# cryobondr-qbit2.net
KiCad netlist of a schematic drawn in EAGLE
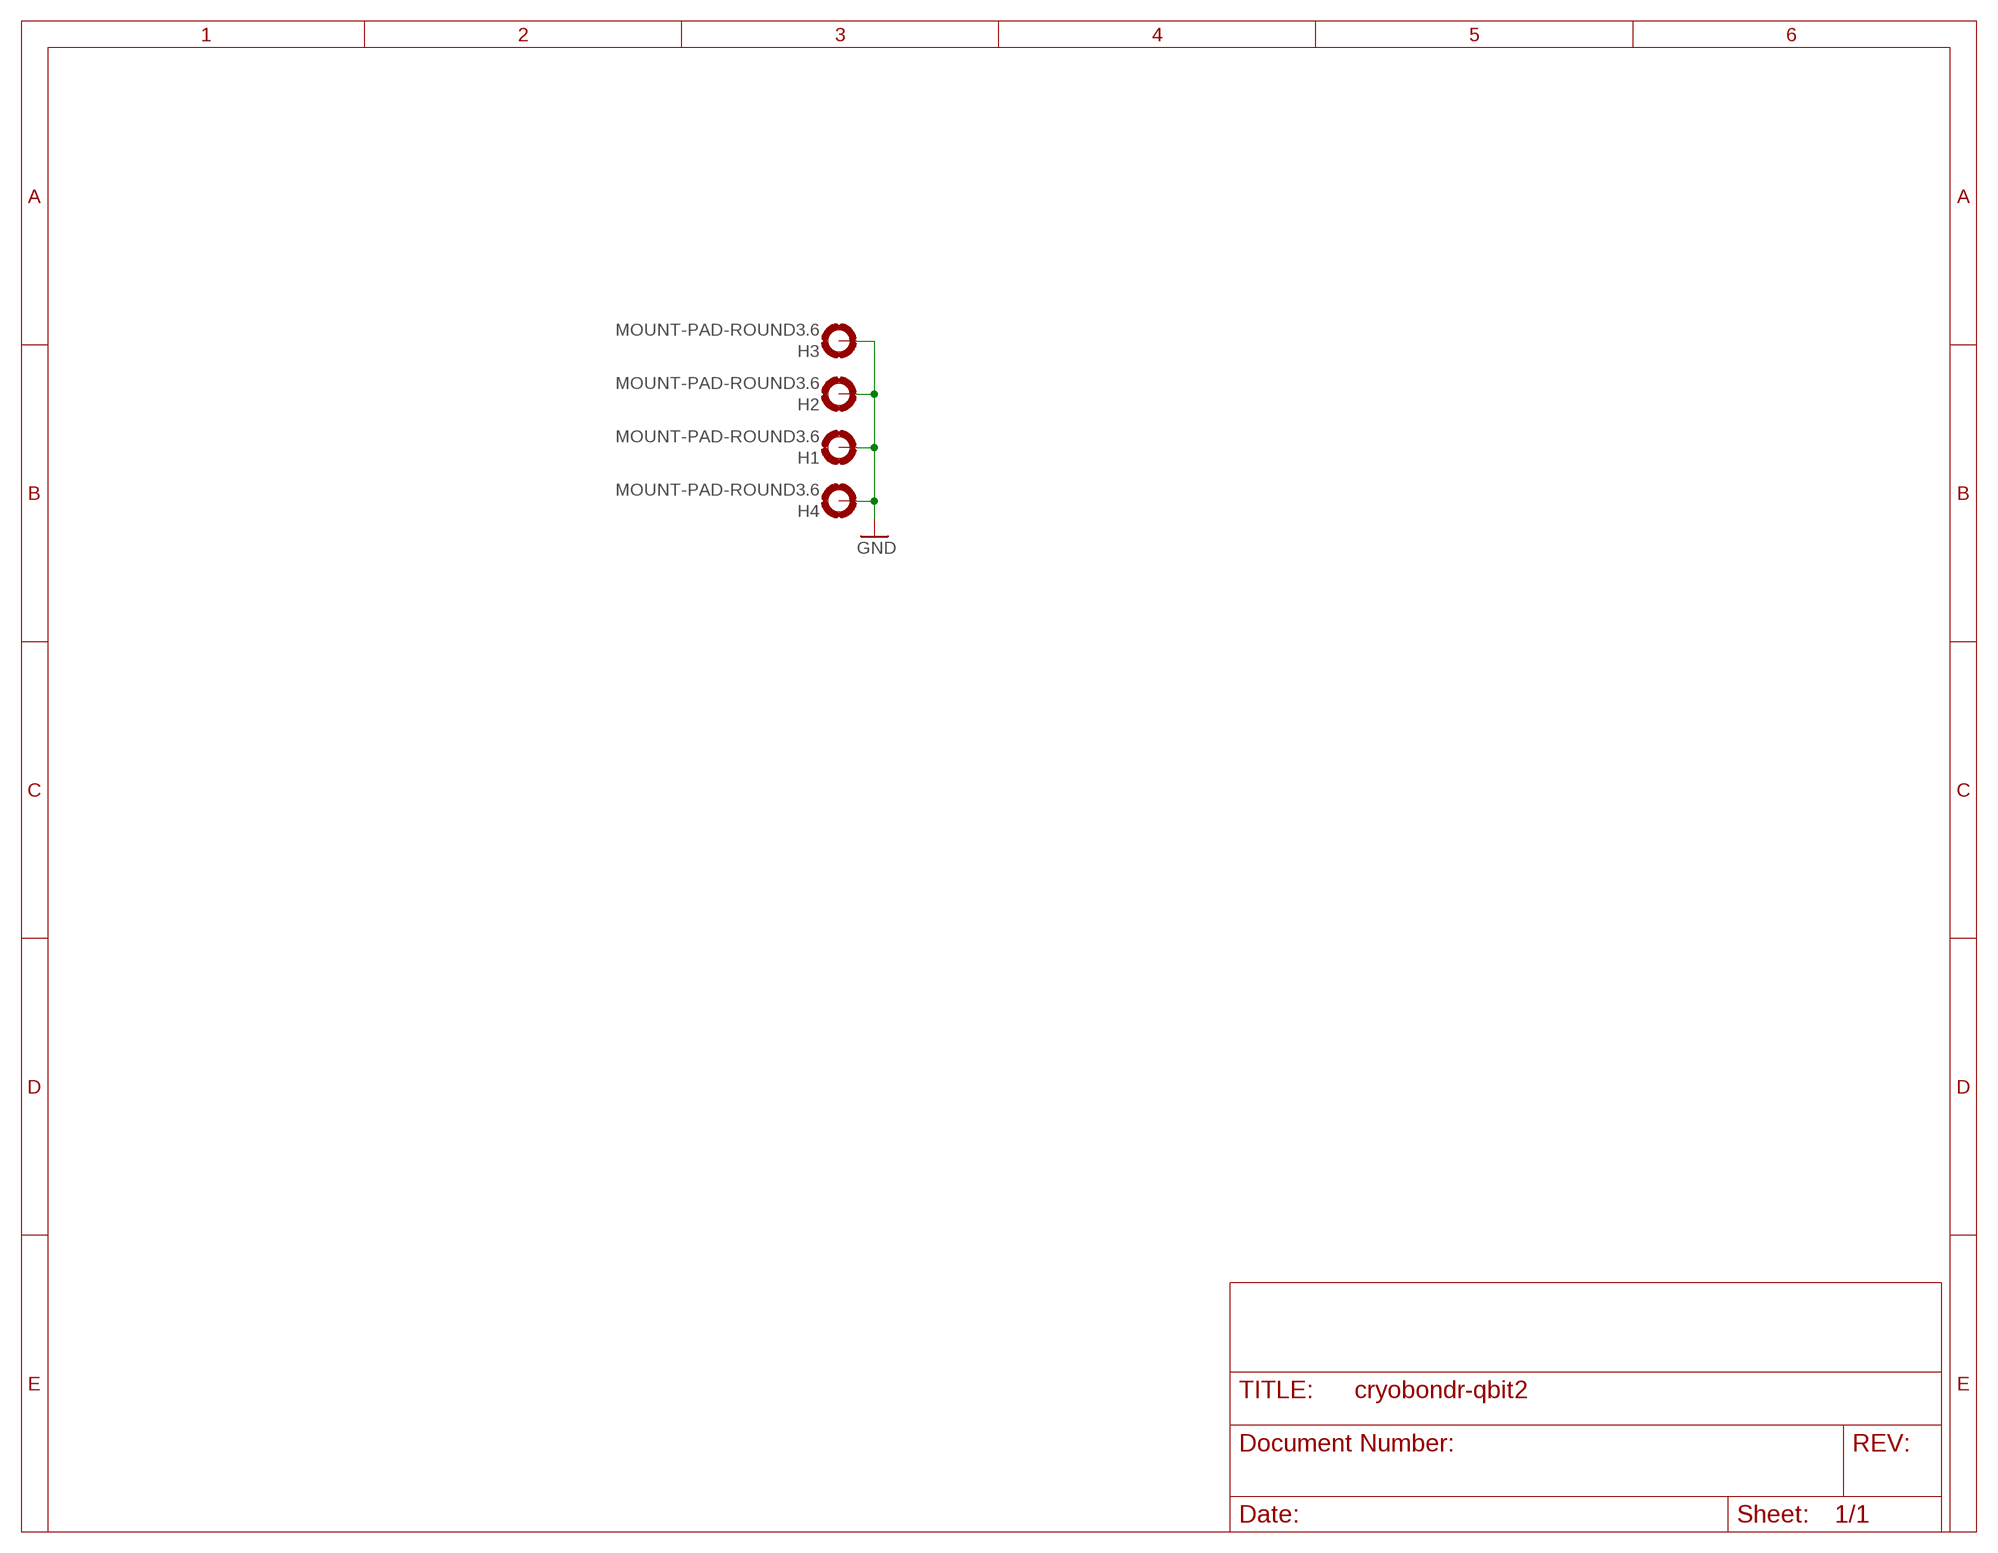
[diagram p0: schematic, sheet 1]

(export (version "E")
  (design (tool "Eeschema 10.0.6"))
  (components
    (comp (ref "H1")
      (value "MOUNT-PAD-ROUND3.6")
      (footprint "eagle-import:3,6-PAD")
      (libsource (lib "eagle-import") (part "MOUNT-PAD-ROUND3.6"))
    )
    (comp (ref "H2")
      (value "MOUNT-PAD-ROUND3.6")
      (footprint "eagle-import:3,6-PAD")
      (libsource (lib "eagle-import") (part "MOUNT-PAD-ROUND3.6"))
    )
    (comp (ref "H3")
      (value "MOUNT-PAD-ROUND3.6")
      (footprint "eagle-import:3,6-PAD")
      (libsource (lib "eagle-import") (part "MOUNT-PAD-ROUND3.6"))
    )
    (comp (ref "H4")
      (value "MOUNT-PAD-ROUND3.6")
      (footprint "eagle-import:3,6-PAD")
      (libsource (lib "eagle-import") (part "MOUNT-PAD-ROUND3.6"))
    )
  )
  (nets
    (net (code "1") (name "GND") (class "Default")
      (node (ref "H1") (pin "B3,6") (pinfunction "MOUNT_B3,6") (pintype "passive"))
      (node (ref "H2") (pin "B3,6") (pinfunction "MOUNT_B3,6") (pintype "passive"))
      (node (ref "H3") (pin "B3,6") (pinfunction "MOUNT_B3,6") (pintype "passive"))
      (node (ref "H4") (pin "B3,6") (pinfunction "MOUNT_B3,6") (pintype "passive"))
    )
  )
)
